# SensorBoard.net
KiCad netlist of a schematic drawn in EAGLE
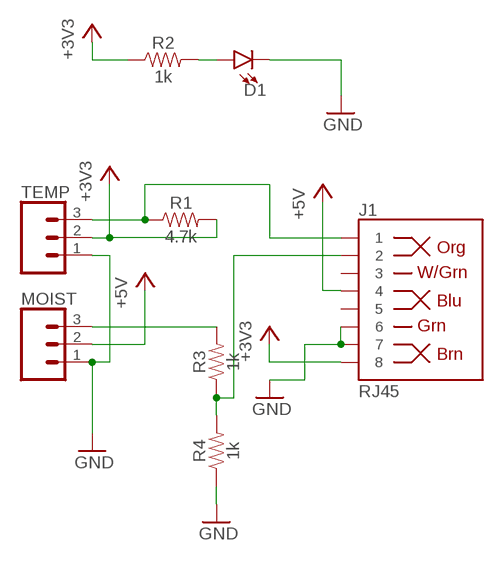
[diagram p0: schematic, sheet 1]

(export (version "E")
  (design (tool "Eeschema 10.0.6"))
  (components
    (comp (ref "D1")
      (value "LED3MM")
      (footprint "eagle-import:LED_3MM")
      (libsource (lib "eagle-import") (part "LED3MM"))
    )
    (comp (ref "J1")
      (value "RJ45")
      (footprint "eagle-import:RJ45-8")
      (libsource (lib "eagle-import") (part "RJ45-8"))
    )
    (comp (ref "MOIST")
      (value "CONN_03")
      (footprint "eagle-import:1X03")
      (libsource (lib "eagle-import") (part "CONN_03"))
    )
    (comp (ref "R1")
      (value "4.7k")
      (footprint "eagle-import:AXIAL-0.3")
      (libsource (lib "eagle-import") (part "1KOHM-HORIZ-1/4W-1%"))
    )
    (comp (ref "R2")
      (value "1k")
      (footprint "eagle-import:AXIAL-0.3")
      (libsource (lib "eagle-import") (part "1KOHM-HORIZ-1/4W-1%"))
    )
    (comp (ref "R3")
      (value "1k")
      (footprint "eagle-import:AXIAL-0.3")
      (libsource (lib "eagle-import") (part "1KOHM-HORIZ-1/4W-1%"))
    )
    (comp (ref "R4")
      (value "1k")
      (footprint "eagle-import:AXIAL-0.3")
      (libsource (lib "eagle-import") (part "1KOHM-HORIZ-1/4W-1%"))
    )
    (comp (ref "TEMP")
      (value "CONN_03")
      (footprint "eagle-import:1X03")
      (libsource (lib "eagle-import") (part "CONN_03"))
    )
  )
  (nets
    (net (code "1") (name "+3V3") (class "Default")
      (node (ref "J1") (pin "8") (pinfunction "8_8") (pintype "bidirectional"))
      (node (ref "R1") (pin "P$2") (pinfunction "2_P$2") (pintype "passive"))
      (node (ref "R2") (pin "P$1") (pinfunction "1_P$1") (pintype "passive"))
      (node (ref "TEMP") (pin "2") (pinfunction "2_2") (pintype "passive"))
    )
    (net (code "2") (name "+5V") (class "Default")
      (node (ref "J1") (pin "4") (pinfunction "4_4") (pintype "bidirectional"))
      (node (ref "MOIST") (pin "2") (pinfunction "2_2") (pintype "passive"))
    )
    (net (code "3") (name "GND") (class "Default")
      (node (ref "D1") (pin "K") (pinfunction "C_K") (pintype "passive"))
      (node (ref "J1") (pin "6") (pinfunction "6_6") (pintype "bidirectional"))
      (node (ref "J1") (pin "7") (pinfunction "7_7") (pintype "bidirectional"))
      (node (ref "MOIST") (pin "1") (pinfunction "1_1") (pintype "passive"))
      (node (ref "R4") (pin "P$1") (pinfunction "1_P$1") (pintype "passive"))
      (node (ref "TEMP") (pin "1") (pinfunction "1_1") (pintype "passive"))
    )
    (net (code "4") (name "Net-(R1-1)") (class "Default")
      (node (ref "J1") (pin "1") (pinfunction "1_1") (pintype "bidirectional"))
      (node (ref "R1") (pin "P$1") (pinfunction "1_P$1") (pintype "passive"))
      (node (ref "TEMP") (pin "3") (pinfunction "3_3") (pintype "passive"))
    )
    (net (code "5") (name "Net-(R2-2)") (class "Default")
      (node (ref "D1") (pin "A") (pinfunction "A_A") (pintype "passive"))
      (node (ref "R2") (pin "P$2") (pinfunction "2_P$2") (pintype "passive"))
    )
    (net (code "6") (name "Net-(R3-1)") (class "Default")
      (node (ref "J1") (pin "2") (pinfunction "2_2") (pintype "bidirectional"))
      (node (ref "R3") (pin "P$1") (pinfunction "1_P$1") (pintype "passive"))
      (node (ref "R4") (pin "P$2") (pinfunction "2_P$2") (pintype "passive"))
    )
    (net (code "7") (name "Net-(R3-2)") (class "Default")
      (node (ref "MOIST") (pin "3") (pinfunction "3_3") (pintype "passive"))
      (node (ref "R3") (pin "P$2") (pinfunction "2_P$2") (pintype "passive"))
    )
    (net (code "8") (name "unconnected-(J1-Pad3)") (class "Default")
      (node (ref "J1") (pin "3") (pinfunction "3_3") (pintype "bidirectional"))
    )
    (net (code "9") (name "unconnected-(J1-Pad5)") (class "Default")
      (node (ref "J1") (pin "5") (pinfunction "5_5") (pintype "bidirectional"))
    )
  )
)
